# Pop-Up_Keller_Pressure_Sensor_Interface_.net
KiCad netlist of a schematic drawn in EAGLE
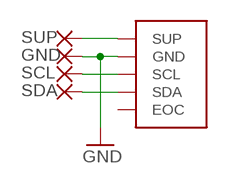
[diagram p0: schematic, sheet 1]

(export (version "E")
  (design (tool "Eeschema 10.0.6"))
  (components
    (comp (ref "GND")
      (value "SMD075X015")
      (footprint "eagle-import:SMD-0,75X0,15")
      (libsource (lib "eagle-import") (part "SMD075X015"))
    )
    (comp (ref "P1")
      (value "4LD")
      (footprint "eagle-import:KELLER-4-LD")
      (libsource (lib "eagle-import") (part "KELLER-4-LD"))
    )
    (comp (ref "SCL")
      (value "SMD075X015")
      (footprint "eagle-import:SMD-0,75X0,15")
      (libsource (lib "eagle-import") (part "SMD075X015"))
    )
    (comp (ref "SDA")
      (value "SMD075X015")
      (footprint "eagle-import:SMD-0,75X0,15")
      (libsource (lib "eagle-import") (part "SMD075X015"))
    )
    (comp (ref "SUP")
      (value "SMD075X015")
      (footprint "eagle-import:SMD-0,75X0,15")
      (libsource (lib "eagle-import") (part "SMD075X015"))
    )
  )
  (nets
    (net (code "1") (name "GND") (class "Default")
      (node (ref "GND") (pin "P$1") (pinfunction "P_P$1") (pintype "passive"))
      (node (ref "P1") (pin "GND") (pinfunction "GND_GND") (pintype "bidirectional"))
    )
    (net (code "2") (name "Net-(SCL-P)") (class "Default")
      (node (ref "P1") (pin "SCL") (pinfunction "SCL_SCL") (pintype "bidirectional"))
      (node (ref "SCL") (pin "P$1") (pinfunction "P_P$1") (pintype "passive"))
    )
    (net (code "3") (name "Net-(SDA-P)") (class "Default")
      (node (ref "P1") (pin "SDA") (pinfunction "SDA_SDA") (pintype "bidirectional"))
      (node (ref "SDA") (pin "P$1") (pinfunction "P_P$1") (pintype "passive"))
    )
    (net (code "4") (name "Net-(SUP-P)") (class "Default")
      (node (ref "P1") (pin "SUP") (pinfunction "SUP_SUP") (pintype "bidirectional"))
      (node (ref "SUP") (pin "P$1") (pinfunction "P_P$1") (pintype "passive"))
    )
    (net (code "5") (name "unconnected-(P1-PadEOC)") (class "Default")
      (node (ref "P1") (pin "EOC") (pinfunction "EOC_EOC") (pintype "bidirectional"))
    )
  )
)
